# USB3_Replication.net
KiCad netlist of a schematic drawn in Altium Designer
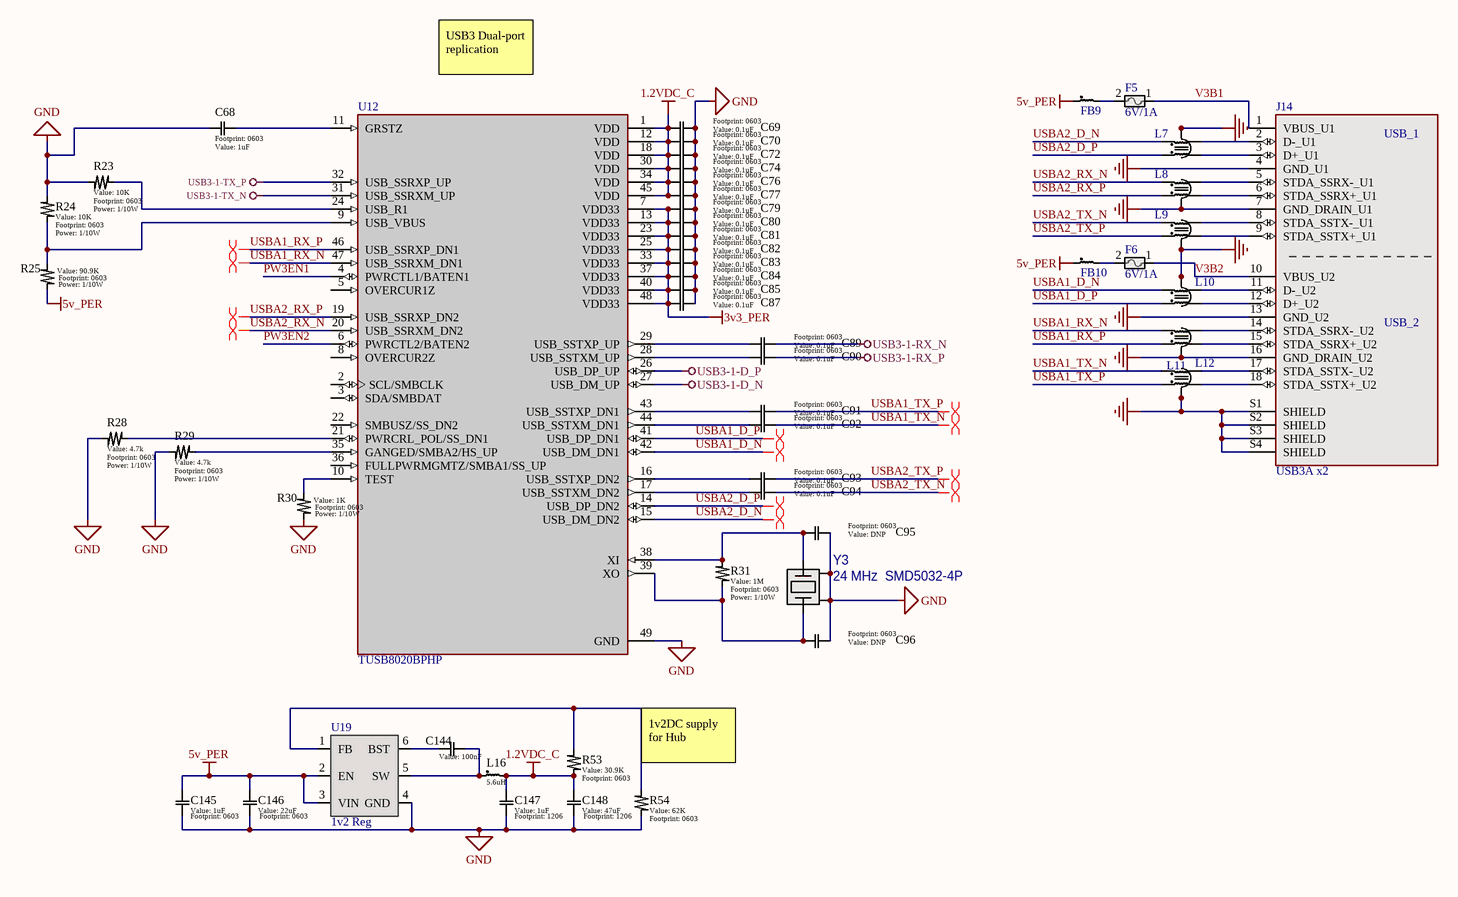
[diagram p0: USB3_Replication.SchDoc]

(export (version "E")
  (design (tool "Eeschema 10.0.6"))
  (components
    (comp (ref "C68")
      (value "1uF")
      (footprint "0603")
      (fields
        (field (name "VOLTAGE") ">10V")
        (field (name "TOLERANCE") "10%")
        (field (name "Comment") "Generic Capacitor")
      )
      (libsource (lib "Capacitors") (part "Generic Capacitor"))
    )
    (comp (ref "C69")
      (value "0.1uF")
      (footprint "0603")
      (fields
        (field (name "VOLTAGE") "10V")
        (field (name "TOLERANCE") "10%")
        (field (name "Comment") "Generic Capacitor")
      )
      (libsource (lib "Capacitors") (part "Generic Capacitor"))
    )
    (comp (ref "C70")
      (value "0.1uF")
      (footprint "0603")
      (fields
        (field (name "VOLTAGE") "10V")
        (field (name "TOLERANCE") "10%")
        (field (name "Comment") "Generic Capacitor")
      )
      (libsource (lib "Capacitors") (part "Generic Capacitor"))
    )
    (comp (ref "C72")
      (value "0.1uF")
      (footprint "0603")
      (fields
        (field (name "VOLTAGE") "10V")
        (field (name "TOLERANCE") "10%")
        (field (name "Comment") "Generic Capacitor")
      )
      (libsource (lib "Capacitors") (part "Generic Capacitor"))
    )
    (comp (ref "C74")
      (value "0.1uF")
      (footprint "0603")
      (fields
        (field (name "VOLTAGE") "10V")
        (field (name "TOLERANCE") "10%")
        (field (name "Comment") "Generic Capacitor")
      )
      (libsource (lib "Capacitors") (part "Generic Capacitor"))
    )
    (comp (ref "C76")
      (value "0.1uF")
      (footprint "0603")
      (fields
        (field (name "VOLTAGE") "10V")
        (field (name "TOLERANCE") "10%")
        (field (name "Comment") "Generic Capacitor")
      )
      (libsource (lib "Capacitors") (part "Generic Capacitor"))
    )
    (comp (ref "C77")
      (value "0.1uF")
      (footprint "0603")
      (fields
        (field (name "VOLTAGE") "10V")
        (field (name "TOLERANCE") "10%")
        (field (name "Comment") "Generic Capacitor")
      )
      (libsource (lib "Capacitors") (part "Generic Capacitor"))
    )
    (comp (ref "C79")
      (value "0.1uF")
      (footprint "0603")
      (fields
        (field (name "VOLTAGE") "10V")
        (field (name "TOLERANCE") "10%")
        (field (name "Comment") "Generic Capacitor")
      )
      (libsource (lib "Capacitors") (part "Generic Capacitor"))
    )
    (comp (ref "C80")
      (value "0.1uF")
      (footprint "0603")
      (fields
        (field (name "VOLTAGE") "10V")
        (field (name "TOLERANCE") "10%")
        (field (name "Comment") "Generic Capacitor")
      )
      (libsource (lib "Capacitors") (part "Generic Capacitor"))
    )
    (comp (ref "C81")
      (value "0.1uF")
      (footprint "0603")
      (fields
        (field (name "VOLTAGE") "10V")
        (field (name "TOLERANCE") "10%")
        (field (name "Comment") "Generic Capacitor")
      )
      (libsource (lib "Capacitors") (part "Generic Capacitor"))
    )
    (comp (ref "C82")
      (value "0.1uF")
      (footprint "0603")
      (fields
        (field (name "VOLTAGE") "10V")
        (field (name "TOLERANCE") "10%")
        (field (name "Comment") "Generic Capacitor")
      )
      (libsource (lib "Capacitors") (part "Generic Capacitor"))
    )
    (comp (ref "C83")
      (value "0.1uF")
      (footprint "0603")
      (fields
        (field (name "VOLTAGE") "10V")
        (field (name "TOLERANCE") "10%")
        (field (name "Comment") "Generic Capacitor")
      )
      (libsource (lib "Capacitors") (part "Generic Capacitor"))
    )
    (comp (ref "C84")
      (value "0.1uF")
      (footprint "0603")
      (fields
        (field (name "VOLTAGE") "10V")
        (field (name "TOLERANCE") "10%")
        (field (name "Comment") "Generic Capacitor")
      )
      (libsource (lib "Capacitors") (part "Generic Capacitor"))
    )
    (comp (ref "C85")
      (value "0.1uF")
      (footprint "0603")
      (fields
        (field (name "VOLTAGE") "10V")
        (field (name "TOLERANCE") "10%")
        (field (name "Comment") "Generic Capacitor")
      )
      (libsource (lib "Capacitors") (part "Generic Capacitor"))
    )
    (comp (ref "C87")
      (value "0.1uF")
      (footprint "0603")
      (fields
        (field (name "VOLTAGE") "10V")
        (field (name "TOLERANCE") "10%")
        (field (name "Comment") "Generic Capacitor")
      )
      (libsource (lib "Capacitors") (part "Generic Capacitor"))
    )
    (comp (ref "C89")
      (value "0.1uF")
      (footprint "0603")
      (fields
        (field (name "VOLTAGE") "10V")
        (field (name "TOLERANCE") "10%")
        (field (name "Comment") "Generic Capacitor")
      )
      (libsource (lib "Capacitors") (part "Generic Capacitor"))
    )
    (comp (ref "C90")
      (value "0.1uF")
      (footprint "0603")
      (fields
        (field (name "VOLTAGE") "10V")
        (field (name "TOLERANCE") "10%")
        (field (name "Comment") "Generic Capacitor")
      )
      (libsource (lib "Capacitors") (part "Generic Capacitor"))
    )
    (comp (ref "C91")
      (value "0.1uF")
      (footprint "0603")
      (fields
        (field (name "VOLTAGE") "10V")
        (field (name "TOLERANCE") "10%")
        (field (name "Comment") "Generic Capacitor")
      )
      (libsource (lib "Capacitors") (part "Generic Capacitor"))
    )
    (comp (ref "C92")
      (value "0.1uF")
      (footprint "0603")
      (fields
        (field (name "VOLTAGE") "10V")
        (field (name "TOLERANCE") "10%")
        (field (name "Comment") "Generic Capacitor")
      )
      (libsource (lib "Capacitors") (part "Generic Capacitor"))
    )
    (comp (ref "C93")
      (value "0.1uF")
      (footprint "0603")
      (fields
        (field (name "VOLTAGE") "10V")
        (field (name "TOLERANCE") "10%")
        (field (name "Comment") "Generic Capacitor")
      )
      (libsource (lib "Capacitors") (part "Generic Capacitor"))
    )
    (comp (ref "C94")
      (value "0.1uF")
      (footprint "0603")
      (fields
        (field (name "VOLTAGE") "10V")
        (field (name "TOLERANCE") "10%")
        (field (name "Comment") "Generic Capacitor")
      )
      (libsource (lib "Capacitors") (part "Generic Capacitor"))
    )
    (comp (ref "C95")
      (value "DNP")
      (footprint "0603")
      (fields
        (field (name "VOLTAGE") ">10V")
        (field (name "TOLERANCE") "10%")
        (field (name "Comment") "Generic Capacitor")
      )
      (libsource (lib "Capacitors") (part "Generic Capacitor"))
    )
    (comp (ref "C96")
      (value "DNP")
      (footprint "0603")
      (fields
        (field (name "VOLTAGE") ">10V")
        (field (name "TOLERANCE") "10%")
        (field (name "Comment") "Generic Capacitor")
      )
      (libsource (lib "Capacitors") (part "Generic Capacitor"))
    )
    (comp (ref "C144")
      (value "100nF")
      (footprint "0603")
      (fields
        (field (name "VOLTAGE") ">10V")
        (field (name "TOLERANCE") "10%")
        (field (name "Comment") "Generic Capacitor")
      )
      (libsource (lib "Capacitors") (part "Generic Capacitor"))
    )
    (comp (ref "C145")
      (value "1uF")
      (footprint "0603")
      (fields
        (field (name "VOLTAGE") ">10V")
        (field (name "TOLERANCE") "10%")
        (field (name "Comment") "Generic Capacitor")
      )
      (libsource (lib "Capacitors") (part "Generic Capacitor"))
    )
    (comp (ref "C146")
      (value "22uF")
      (footprint "0603")
      (fields
        (field (name "VOLTAGE") ">10V")
        (field (name "TOLERANCE") "10%")
        (field (name "Comment") "Generic Capacitor")
      )
      (libsource (lib "Capacitors") (part "Generic Capacitor"))
    )
    (comp (ref "C147")
      (value "1uF")
      (footprint "1206")
      (fields
        (field (name "VOLTAGE") ">10V")
        (field (name "TOLERANCE") "10%")
        (field (name "Comment") "Generic Capacitor")
      )
      (libsource (lib "Capacitors") (part "Generic Capacitor"))
    )
    (comp (ref "C148")
      (value "47uF")
      (footprint "1206")
      (fields
        (field (name "VOLTAGE") ">10V")
        (field (name "TOLERANCE") "10%")
        (field (name "Comment") "Generic Capacitor")
      )
      (libsource (lib "Capacitors") (part "Generic Capacitor"))
    )
    (comp (ref "F5")
      (value "6V/1A")
      (footprint "0805")
      (description "Polymeric PTC Resettable Fuse 6V 1 A Ih Surface Mount 0805 (2012 Metric), Concave")
      (fields (field (name "MANUFACTURER") "Bel") (field (name "MANUFACTURER PART NUMBER") "0ZCK0100FF2E"))
      (libsource (lib "Regulators") (part "0ZCK0100FF2E"))
    )
    (comp (ref "F6")
      (value "6V/1A")
      (footprint "0805")
      (description "Polymeric PTC Resettable Fuse 6V 1 A Ih Surface Mount 0805 (2012 Metric), Concave")
      (fields (field (name "MANUFACTURER") "Bel") (field (name "MANUFACTURER PART NUMBER") "0ZCK0100FF2E"))
      (libsource (lib "Regulators") (part "0ZCK0100FF2E"))
    )
    (comp (ref "FB9")
      (value "0603 Ferrite")
      (footprint "0603")
      (description "120 Ohms @ 100 MHz 1 Signal Line Ferrite Bead 0603 (1608 Metric) 500mA 180mOhm")
      (fields
        (field (name "MANUFACTURER") "Pulse")
        (field (name "MANUFACTURER PART NUMBER") "PE-0603FB121ST")
      )
      (libsource (lib "Inductors") (part "PE-0603FB121ST"))
    )
    (comp (ref "FB10")
      (value "0603 Ferrite")
      (footprint "0603")
      (description "120 Ohms @ 100 MHz 1 Signal Line Ferrite Bead 0603 (1608 Metric) 500mA 180mOhm")
      (fields
        (field (name "MANUFACTURER") "Pulse")
        (field (name "MANUFACTURER PART NUMBER") "PE-0603FB121ST")
      )
      (libsource (lib "Inductors") (part "PE-0603FB121ST"))
    )
    (comp (ref "J14")
      (value "USB3A x2")
      (footprint "0484060003")
      (fields (field (name "MP") "0484060003") (field (name "MF") "Molex"))
      (libsource (lib "Connectors") (part "0484060003"))
    )
    (comp (ref "L7")
      (value "2CH CMC")
      (footprint "SMD-6-2CH")
      (description "35Ω@100MHz -40℃~+85℃ 4Ω 5V 2 100mA SMD Common Mode Filters ROHS")
      (libsource (lib "Inductors") (part "ICMEF112P350MFR"))
    )
    (comp (ref "L8")
      (value "2CH CMC")
      (footprint "SMD-6-2CH")
      (description "35Ω@100MHz -40℃~+85℃ 4Ω 5V 2 100mA SMD Common Mode Filters ROHS")
      (libsource (lib "") (part "ICMEF112P350MFR_1"))
    )
    (comp (ref "L9")
      (value "2CH CMC")
      (footprint "SMD-6-2CH")
      (description "35Ω@100MHz -40℃~+85℃ 4Ω 5V 2 100mA SMD Common Mode Filters ROHS")
      (libsource (lib "") (part "ICMEF112P350MFR_1"))
    )
    (comp (ref "L10")
      (value "2CH CMC")
      (footprint "SMD-6-2CH")
      (description "35Ω@100MHz -40℃~+85℃ 4Ω 5V 2 100mA SMD Common Mode Filters ROHS")
      (libsource (lib "Inductors") (part "ICMEF112P350MFR"))
    )
    (comp (ref "L11")
      (value "2CH CMC")
      (footprint "SMD-6-2CH")
      (description "35Ω@100MHz -40℃~+85℃ 4Ω 5V 2 100mA SMD Common Mode Filters ROHS")
      (libsource (lib "") (part "ICMEF112P350MFR_1"))
    )
    (comp (ref "L12")
      (value "2CH CMC")
      (footprint "SMD-6-2CH")
      (description "35Ω@100MHz -40℃~+85℃ 4Ω 5V 2 100mA SMD Common Mode Filters ROHS")
      (libsource (lib "") (part "ICMEF112P350MFR_1"))
    )
    (comp (ref "L16")
      (value "5.6uH")
      (footprint "TMPC0402HP")
      (description "2A 5.6uH ±20% SMD Power Inductor")
      (libsource (lib "Inductors") (part "TMPC0402HP-5R6MG-Z02"))
    )
    (comp (ref "R23")
      (value "10K")
      (footprint "0603")
      (fields
        (field (name "TOLERANCE") "1%")
        (field (name "POWER") "1/10W")
        (field (name "Comment") "Generic Resistor")
      )
      (libsource (lib "Resistors") (part "Generic Resistor"))
    )
    (comp (ref "R24")
      (value "10K")
      (footprint "0603")
      (fields
        (field (name "TOLERANCE") "1%")
        (field (name "POWER") "1/10W")
        (field (name "Comment") "Generic Resistor")
      )
      (libsource (lib "Resistors") (part "Generic Resistor"))
    )
    (comp (ref "R25")
      (value "90.9K")
      (footprint "0603")
      (fields
        (field (name "TOLERANCE") "1%")
        (field (name "POWER") "1/10W")
        (field (name "Comment") "Generic Resistor")
      )
      (libsource (lib "Resistors") (part "Generic Resistor"))
    )
    (comp (ref "R28")
      (value "4.7k")
      (footprint "0603")
      (fields
        (field (name "TOLERANCE") "1%")
        (field (name "POWER") "1/10W")
        (field (name "Comment") "Generic Resistor")
      )
      (libsource (lib "Resistors") (part "Generic Resistor"))
    )
    (comp (ref "R29")
      (value "4.7k")
      (footprint "0603")
      (fields
        (field (name "TOLERANCE") "1%")
        (field (name "POWER") "1/10W")
        (field (name "Comment") "Generic Resistor")
      )
      (libsource (lib "Resistors") (part "Generic Resistor"))
    )
    (comp (ref "R30")
      (value "1K")
      (footprint "0603")
      (fields
        (field (name "TOLERANCE") "1%")
        (field (name "POWER") "1/10W")
        (field (name "Comment") "Generic Resistor")
      )
      (libsource (lib "Resistors") (part "Generic Resistor"))
    )
    (comp (ref "R31")
      (value "1M")
      (footprint "0603")
      (fields
        (field (name "TOLERANCE") "1%")
        (field (name "POWER") "1/10W")
        (field (name "Comment") "Generic Resistor")
      )
      (libsource (lib "Resistors") (part "Generic Resistor"))
    )
    (comp (ref "R53")
      (value "30.9K")
      (footprint "0603")
      (fields
        (field (name "TOLERANCE") "1%")
        (field (name "POWER") "1/10W")
        (field (name "Comment") "Generic Resistor")
      )
      (libsource (lib "Resistors") (part "Generic Resistor"))
    )
    (comp (ref "R54")
      (value "62K")
      (footprint "0603")
      (fields
        (field (name "TOLERANCE") "1%")
        (field (name "POWER") "1/10W")
        (field (name "Comment") "Generic Resistor")
      )
      (libsource (lib "Resistors") (part "Generic Resistor"))
    )
    (comp (ref "U12")
      (value "TUSB8020BPHP")
      (footprint "HTQFP-48(7x7)")
      (description "USB Hub Controller USB 3.0")
      (libsource (lib "Misc ICs") (part "TUSB8020BPHP"))
    )
    (comp (ref "U19")
      (value "1v2 Reg")
      (footprint "TSOT-23-6")
      (description "Step-down type Adjustable 2A 1.2V~12V 3.8V~32V TSOT-23-6 DC-DC Converter")
      (libsource (lib "Regulators") (part "AP63201WU-7"))
    )
    (comp (ref "Y3")
      (value "24 MHz  SMD5032-4P")
      (footprint "ECS-240-18-30BQ-DS")
      (description "24 MHz ±30ppm Crystal 18pF 30 Ohms 4-SMD, No Lead")
      (libsource (lib "Gamber - Johnson LLC") (part "ECS-240-18-30BQ-DS"))
    )
  )
  (nets
    (net (code "1") (name "/PW3EN1") (class "Default")
      (node (ref "U12") (pin "4") (pinfunction "PWRCTL1/BATEN1_4") (pintype "bidirectional"))
    )
    (net (code "2") (name "/PW3EN2") (class "Default")
      (node (ref "U12") (pin "6") (pinfunction "PWRCTL2/BATEN2_6") (pintype "bidirectional"))
    )
    (net (code "3") (name "/USBA1_D_N") (class "Default")
      (node (ref "L10") (pin "2") (pinfunction "2_2") (pintype "passive"))
      (node (ref "U12") (pin "42") (pinfunction "USB_DM_DN1_42") (pintype "bidirectional"))
    )
    (net (code "4") (name "/USBA1_D_P") (class "Default")
      (node (ref "L10") (pin "1") (pinfunction "1_1") (pintype "passive"))
      (node (ref "U12") (pin "41") (pinfunction "USB_DP_DN1_41") (pintype "bidirectional"))
    )
    (net (code "5") (name "/USBA1_RX_N") (class "Default")
      (node (ref "L11") (pin "1") (pinfunction "1_1") (pintype "passive"))
      (node (ref "U12") (pin "47") (pinfunction "USB_SSRXM_DN1_47") (pintype "input"))
    )
    (net (code "6") (name "/USBA1_RX_P") (class "Default")
      (node (ref "L11") (pin "2") (pinfunction "2_2") (pintype "passive"))
      (node (ref "U12") (pin "46") (pinfunction "USB_SSRXP_DN1_46") (pintype "input"))
    )
    (net (code "7") (name "/USBA1_TX_N") (class "Default")
      (node (ref "C92") (pin "1") (pinfunction "1_1") (pintype "passive"))
      (node (ref "L12") (pin "1") (pinfunction "1_1") (pintype "passive"))
    )
    (net (code "8") (name "/USBA1_TX_P") (class "Default")
      (node (ref "C91") (pin "1") (pinfunction "1_1") (pintype "passive"))
      (node (ref "L12") (pin "2") (pinfunction "2_2") (pintype "passive"))
    )
    (net (code "9") (name "/USBA2_D_N") (class "Default")
      (node (ref "L7") (pin "2") (pinfunction "2_2") (pintype "passive"))
      (node (ref "U12") (pin "15") (pinfunction "USB_DM_DN2_15") (pintype "bidirectional"))
    )
    (net (code "10") (name "/USBA2_D_P") (class "Default")
      (node (ref "L7") (pin "1") (pinfunction "1_1") (pintype "passive"))
      (node (ref "U12") (pin "14") (pinfunction "USB_DP_DN2_14") (pintype "bidirectional"))
    )
    (net (code "11") (name "/USBA2_RX_N") (class "Default")
      (node (ref "L8") (pin "1") (pinfunction "1_1") (pintype "passive"))
      (node (ref "U12") (pin "20") (pinfunction "USB_SSRXM_DN2_20") (pintype "input"))
    )
    (net (code "12") (name "/USBA2_RX_P") (class "Default")
      (node (ref "L8") (pin "2") (pinfunction "2_2") (pintype "passive"))
      (node (ref "U12") (pin "19") (pinfunction "USB_SSRXP_DN2_19") (pintype "input"))
    )
    (net (code "13") (name "/USBA2_TX_N") (class "Default")
      (node (ref "C94") (pin "1") (pinfunction "1_1") (pintype "passive"))
      (node (ref "L9") (pin "1") (pinfunction "1_1") (pintype "passive"))
    )
    (net (code "14") (name "/USBA2_TX_P") (class "Default")
      (node (ref "C93") (pin "1") (pinfunction "1_1") (pintype "passive"))
      (node (ref "L9") (pin "2") (pinfunction "2_2") (pintype "passive"))
    )
    (net (code "15") (name "/V3B1") (class "Default")
      (node (ref "F5") (pin "1") (pinfunction "1_1") (pintype "passive"))
      (node (ref "J14") (pin "1") (pinfunction "VBUS_U1_1") (pintype "power_in"))
    )
    (net (code "16") (name "/V3B2") (class "Default")
      (node (ref "F6") (pin "1") (pinfunction "1_1") (pintype "passive"))
      (node (ref "J14") (pin "10") (pinfunction "VBUS_U2_10") (pintype "power_in"))
    )
    (net (code "17") (name "1.2VDC_C") (class "Default")
      (node (ref "C147") (pin "1") (pinfunction "1_1") (pintype "passive"))
      (node (ref "C148") (pin "1") (pinfunction "1_1") (pintype "passive"))
      (node (ref "C69") (pin "2") (pinfunction "2_2") (pintype "passive"))
      (node (ref "C70") (pin "2") (pinfunction "2_2") (pintype "passive"))
      (node (ref "C72") (pin "2") (pinfunction "2_2") (pintype "passive"))
      (node (ref "C74") (pin "2") (pinfunction "2_2") (pintype "passive"))
      (node (ref "C76") (pin "2") (pinfunction "2_2") (pintype "passive"))
      (node (ref "C77") (pin "2") (pinfunction "2_2") (pintype "passive"))
      (node (ref "L16") (pin "2") (pinfunction "2_2") (pintype "passive"))
      (node (ref "R53") (pin "1") (pinfunction "1_1") (pintype "passive"))
      (node (ref "U12") (pin "1") (pinfunction "VDD_1") (pintype "power_in"))
      (node (ref "U12") (pin "12") (pinfunction "VDD_12") (pintype "power_in"))
      (node (ref "U12") (pin "18") (pinfunction "VDD_18") (pintype "power_in"))
      (node (ref "U12") (pin "30") (pinfunction "VDD_30") (pintype "power_in"))
      (node (ref "U12") (pin "34") (pinfunction "VDD_34") (pintype "power_in"))
      (node (ref "U12") (pin "45") (pinfunction "VDD_45") (pintype "power_in"))
    )
    (net (code "18") (name "3v3_PER") (class "Default")
      (node (ref "C79") (pin "2") (pinfunction "2_2") (pintype "passive"))
      (node (ref "C80") (pin "2") (pinfunction "2_2") (pintype "passive"))
      (node (ref "C81") (pin "2") (pinfunction "2_2") (pintype "passive"))
      (node (ref "C82") (pin "2") (pinfunction "2_2") (pintype "passive"))
      (node (ref "C83") (pin "2") (pinfunction "2_2") (pintype "passive"))
      (node (ref "C84") (pin "2") (pinfunction "2_2") (pintype "passive"))
      (node (ref "C85") (pin "2") (pinfunction "2_2") (pintype "passive"))
      (node (ref "C87") (pin "2") (pinfunction "2_2") (pintype "passive"))
      (node (ref "U12") (pin "13") (pinfunction "VDD33_13") (pintype "power_in"))
      (node (ref "U12") (pin "23") (pinfunction "VDD33_23") (pintype "power_in"))
      (node (ref "U12") (pin "25") (pinfunction "VDD33_25") (pintype "power_in"))
      (node (ref "U12") (pin "33") (pinfunction "VDD33_33") (pintype "power_in"))
      (node (ref "U12") (pin "37") (pinfunction "VDD33_37") (pintype "power_in"))
      (node (ref "U12") (pin "40") (pinfunction "VDD33_40") (pintype "power_in"))
      (node (ref "U12") (pin "48") (pinfunction "VDD33_48") (pintype "power_in"))
      (node (ref "U12") (pin "7") (pinfunction "VDD33_7") (pintype "power_in"))
    )
    (net (code "19") (name "5v_PER") (class "Default")
      (node (ref "C145") (pin "1") (pinfunction "1_1") (pintype "passive"))
      (node (ref "C146") (pin "1") (pinfunction "1_1") (pintype "passive"))
      (node (ref "FB10") (pin "1") (pinfunction "1_1") (pintype "passive"))
      (node (ref "FB9") (pin "1") (pinfunction "1_1") (pintype "passive"))
      (node (ref "R25") (pin "1") (pinfunction "1_1") (pintype "passive"))
      (node (ref "U19") (pin "2") (pinfunction "EN_2") (pintype "passive"))
      (node (ref "U19") (pin "3") (pinfunction "VIN_3") (pintype "passive"))
    )
    (net (code "20") (name "GND") (class "Default")
      (node (ref "C145") (pin "2") (pinfunction "2_2") (pintype "passive"))
      (node (ref "C146") (pin "2") (pinfunction "2_2") (pintype "passive"))
      (node (ref "C147") (pin "2") (pinfunction "2_2") (pintype "passive"))
      (node (ref "C148") (pin "2") (pinfunction "2_2") (pintype "passive"))
      (node (ref "C68") (pin "1") (pinfunction "1_1") (pintype "passive"))
      (node (ref "C69") (pin "1") (pinfunction "1_1") (pintype "passive"))
      (node (ref "C70") (pin "1") (pinfunction "1_1") (pintype "passive"))
      (node (ref "C72") (pin "1") (pinfunction "1_1") (pintype "passive"))
      (node (ref "C74") (pin "1") (pinfunction "1_1") (pintype "passive"))
      (node (ref "C76") (pin "1") (pinfunction "1_1") (pintype "passive"))
      (node (ref "C77") (pin "1") (pinfunction "1_1") (pintype "passive"))
      (node (ref "C79") (pin "1") (pinfunction "1_1") (pintype "passive"))
      (node (ref "C80") (pin "1") (pinfunction "1_1") (pintype "passive"))
      (node (ref "C81") (pin "1") (pinfunction "1_1") (pintype "passive"))
      (node (ref "C82") (pin "1") (pinfunction "1_1") (pintype "passive"))
      (node (ref "C83") (pin "1") (pinfunction "1_1") (pintype "passive"))
      (node (ref "C84") (pin "1") (pinfunction "1_1") (pintype "passive"))
      (node (ref "C85") (pin "1") (pinfunction "1_1") (pintype "passive"))
      (node (ref "C87") (pin "1") (pinfunction "1_1") (pintype "passive"))
      (node (ref "C95") (pin "1") (pinfunction "1_1") (pintype "passive"))
      (node (ref "C96") (pin "1") (pinfunction "1_1") (pintype "passive"))
      (node (ref "J14") (pin "13") (pinfunction "GND_U2_13") (pintype "power_in"))
      (node (ref "J14") (pin "16") (pinfunction "GND_DRAIN_U2_16") (pintype "power_in"))
      (node (ref "J14") (pin "4") (pinfunction "GND_U1_4") (pintype "power_in"))
      (node (ref "J14") (pin "7") (pinfunction "GND_DRAIN_U1_7") (pintype "power_in"))
      (node (ref "J14") (pin "S1") (pinfunction "SHIELD_S1") (pintype "passive"))
      (node (ref "J14") (pin "S2") (pinfunction "SHIELD_S2") (pintype "passive"))
      (node (ref "J14") (pin "S3") (pinfunction "SHIELD_S3") (pintype "passive"))
      (node (ref "J14") (pin "S4") (pinfunction "SHIELD_S4") (pintype "passive"))
      (node (ref "L10") (pin "5") (pinfunction "5_5") (pintype "passive"))
      (node (ref "L10") (pin "6") (pinfunction "6_6") (pintype "passive"))
      (node (ref "L11") (pin "5") (pinfunction "5_5") (pintype "passive"))
      (node (ref "L11") (pin "6") (pinfunction "6_6") (pintype "passive"))
      (node (ref "L12") (pin "5") (pinfunction "5_5") (pintype "passive"))
      (node (ref "L12") (pin "6") (pinfunction "6_6") (pintype "passive"))
      (node (ref "L7") (pin "5") (pinfunction "5_5") (pintype "passive"))
      (node (ref "L7") (pin "6") (pinfunction "6_6") (pintype "passive"))
      (node (ref "L8") (pin "5") (pinfunction "5_5") (pintype "passive"))
      (node (ref "L8") (pin "6") (pinfunction "6_6") (pintype "passive"))
      (node (ref "L9") (pin "5") (pinfunction "5_5") (pintype "passive"))
      (node (ref "L9") (pin "6") (pinfunction "6_6") (pintype "passive"))
      (node (ref "R23") (pin "1") (pinfunction "1_1") (pintype "passive"))
      (node (ref "R24") (pin "1") (pinfunction "1_1") (pintype "passive"))
      (node (ref "R28") (pin "1") (pinfunction "1_1") (pintype "passive"))
      (node (ref "R29") (pin "1") (pinfunction "1_1") (pintype "passive"))
      (node (ref "R30") (pin "1") (pinfunction "1_1") (pintype "passive"))
      (node (ref "R54") (pin "1") (pinfunction "1_1") (pintype "passive"))
      (node (ref "U12") (pin "49") (pinfunction "GND_49") (pintype "power_in"))
      (node (ref "U19") (pin "4") (pinfunction "GND_4") (pintype "power_in"))
      (node (ref "Y3") (pin "2") (pinfunction "GND_2") (pintype "power_in"))
      (node (ref "Y3") (pin "4") (pinfunction "GND_4") (pintype "power_in"))
    )
    (net (code "21") (name "Net-(F5-Pad2)") (class "Default")
      (node (ref "F5") (pin "2") (pinfunction "2_2") (pintype "passive"))
      (node (ref "FB9") (pin "2") (pinfunction "2_2") (pintype "passive"))
    )
    (net (code "22") (name "Net-(F6-Pad2)") (class "Default")
      (node (ref "F6") (pin "2") (pinfunction "2_2") (pintype "passive"))
      (node (ref "FB10") (pin "2") (pinfunction "2_2") (pintype "passive"))
    )
    (net (code "23") (name "Net-(J14-D+_U1)") (class "Default")
      (node (ref "J14") (pin "3") (pinfunction "D+_U1_3") (pintype "bidirectional"))
      (node (ref "L7") (pin "4") (pinfunction "4_4") (pintype "passive"))
    )
    (net (code "24") (name "Net-(J14-D+_U2)") (class "Default")
      (node (ref "J14") (pin "12") (pinfunction "D+_U2_12") (pintype "bidirectional"))
      (node (ref "L10") (pin "4") (pinfunction "4_4") (pintype "passive"))
    )
    (net (code "25") (name "Net-(J14-D-_U1)") (class "Default")
      (node (ref "J14") (pin "2") (pinfunction "D-_U1_2") (pintype "bidirectional"))
      (node (ref "L7") (pin "3") (pinfunction "3_3") (pintype "passive"))
    )
    (net (code "26") (name "Net-(J14-D-_U2)") (class "Default")
      (node (ref "J14") (pin "11") (pinfunction "D-_U2_11") (pintype "bidirectional"))
      (node (ref "L10") (pin "3") (pinfunction "3_3") (pintype "passive"))
    )
    (net (code "27") (name "Net-(J14-STDA_SSRX+_U1)") (class "Default")
      (node (ref "J14") (pin "6") (pinfunction "STDA_SSRX+_U1_6") (pintype "bidirectional"))
      (node (ref "L8") (pin "3") (pinfunction "3_3") (pintype "passive"))
    )
    (net (code "28") (name "Net-(J14-STDA_SSRX+_U2)") (class "Default")
      (node (ref "J14") (pin "15") (pinfunction "STDA_SSRX+_U2_15") (pintype "bidirectional"))
      (node (ref "L11") (pin "3") (pinfunction "3_3") (pintype "passive"))
    )
    (net (code "29") (name "Net-(J14-STDA_SSRX-_U1)") (class "Default")
      (node (ref "J14") (pin "5") (pinfunction "STDA_SSRX-_U1_5") (pintype "bidirectional"))
      (node (ref "L8") (pin "4") (pinfunction "4_4") (pintype "passive"))
    )
    (net (code "30") (name "Net-(J14-STDA_SSRX-_U2)") (class "Default")
      (node (ref "J14") (pin "14") (pinfunction "STDA_SSRX-_U2_14") (pintype "bidirectional"))
      (node (ref "L11") (pin "4") (pinfunction "4_4") (pintype "passive"))
    )
    (net (code "31") (name "Net-(J14-STDA_SSTX+_U1)") (class "Default")
      (node (ref "J14") (pin "9") (pinfunction "STDA_SSTX+_U1_9") (pintype "bidirectional"))
      (node (ref "L9") (pin "3") (pinfunction "3_3") (pintype "passive"))
    )
    (net (code "32") (name "Net-(J14-STDA_SSTX+_U2)") (class "Default")
      (node (ref "J14") (pin "18") (pinfunction "STDA_SSTX+_U2_18") (pintype "bidirectional"))
      (node (ref "L12") (pin "3") (pinfunction "3_3") (pintype "passive"))
    )
    (net (code "33") (name "Net-(J14-STDA_SSTX-_U1)") (class "Default")
      (node (ref "J14") (pin "8") (pinfunction "STDA_SSTX-_U1_8") (pintype "bidirectional"))
      (node (ref "L9") (pin "4") (pinfunction "4_4") (pintype "passive"))
    )
    (net (code "34") (name "Net-(J14-STDA_SSTX-_U2)") (class "Default")
      (node (ref "J14") (pin "17") (pinfunction "STDA_SSTX-_U2_17") (pintype "bidirectional"))
      (node (ref "L12") (pin "4") (pinfunction "4_4") (pintype "passive"))
    )
    (net (code "35") (name "Net-(U12-GANGED{slash}SMBA2{slash}HS_UP)") (class "Default")
      (node (ref "R29") (pin "2") (pinfunction "2_2") (pintype "passive"))
      (node (ref "U12") (pin "35") (pinfunction "GANGED/SMBA2/HS_UP_35") (pintype "input"))
    )
    (net (code "36") (name "Net-(U12-GRSTZ)") (class "Default")
      (node (ref "C68") (pin "2") (pinfunction "2_2") (pintype "passive"))
      (node (ref "U12") (pin "11") (pinfunction "GRSTZ_11") (pintype "input"))
    )
    (net (code "37") (name "Net-(U12-PWRCRL_POL{slash}SS_DN1)") (class "Default")
      (node (ref "R28") (pin "2") (pinfunction "2_2") (pintype "passive"))
      (node (ref "U12") (pin "21") (pinfunction "PWRCRL_POL/SS_DN1_21") (pintype "bidirectional"))
    )
    (net (code "38") (name "Net-(U12-TEST)") (class "Default")
      (node (ref "R30") (pin "2") (pinfunction "2_2") (pintype "passive"))
      (node (ref "U12") (pin "10") (pinfunction "TEST_10") (pintype "input"))
    )
    (net (code "39") (name "Net-(U12-USB_R1)") (class "Default")
      (node (ref "R23") (pin "2") (pinfunction "2_2") (pintype "passive"))
      (node (ref "U12") (pin "24") (pinfunction "USB_R1_24") (pintype "input"))
    )
    (net (code "40") (name "Net-(U12-USB_SSTXM_DN1)") (class "Default")
      (node (ref "C92") (pin "2") (pinfunction "2_2") (pintype "passive"))
      (node (ref "U12") (pin "44") (pinfunction "USB_SSTXM_DN1_44") (pintype "output"))
    )
    (net (code "41") (name "Net-(U12-USB_SSTXM_DN2)") (class "Default")
      (node (ref "C94") (pin "2") (pinfunction "2_2") (pintype "passive"))
      (node (ref "U12") (pin "17") (pinfunction "USB_SSTXM_DN2_17") (pintype "output"))
    )
    (net (code "42") (name "Net-(U12-USB_SSTXM_UP)") (class "Default")
      (node (ref "C90") (pin "2") (pinfunction "2_2") (pintype "passive"))
      (node (ref "U12") (pin "28") (pinfunction "USB_SSTXM_UP_28") (pintype "output"))
    )
    (net (code "43") (name "Net-(U12-USB_SSTXP_DN1)") (class "Default")
      (node (ref "C91") (pin "2") (pinfunction "2_2") (pintype "passive"))
      (node (ref "U12") (pin "43") (pinfunction "USB_SSTXP_DN1_43") (pintype "output"))
    )
    (net (code "44") (name "Net-(U12-USB_SSTXP_DN2)") (class "Default")
      (node (ref "C93") (pin "2") (pinfunction "2_2") (pintype "passive"))
      (node (ref "U12") (pin "16") (pinfunction "USB_SSTXP_DN2_16") (pintype "output"))
    )
    (net (code "45") (name "Net-(U12-USB_SSTXP_UP)") (class "Default")
      (node (ref "C89") (pin "2") (pinfunction "2_2") (pintype "passive"))
      (node (ref "U12") (pin "29") (pinfunction "USB_SSTXP_UP_29") (pintype "output"))
    )
    (net (code "46") (name "Net-(U12-USB_VBUS)") (class "Default")
      (node (ref "R24") (pin "2") (pinfunction "2_2") (pintype "passive"))
      (node (ref "R25") (pin "2") (pinfunction "2_2") (pintype "passive"))
      (node (ref "U12") (pin "9") (pinfunction "USB_VBUS_9") (pintype "input"))
    )
    (net (code "47") (name "Net-(U12-XI)") (class "Default")
      (node (ref "C95") (pin "2") (pinfunction "2_2") (pintype "passive"))
      (node (ref "R31") (pin "1") (pinfunction "1_1") (pintype "passive"))
      (node (ref "U12") (pin "38") (pinfunction "XI_38") (pintype "input"))
      (node (ref "Y3") (pin "3") (pintype "passive"))
    )
    (net (code "48") (name "Net-(U12-XO)") (class "Default")
      (node (ref "C96") (pin "2") (pinfunction "2_2") (pintype "passive"))
      (node (ref "R31") (pin "2") (pinfunction "2_2") (pintype "passive"))
      (node (ref "U12") (pin "39") (pinfunction "XO_39") (pintype "output"))
      (node (ref "Y3") (pin "1") (pintype "passive"))
    )
    (net (code "49") (name "Net-(U19-BST)") (class "Default")
      (node (ref "C144") (pin "1") (pinfunction "1_1") (pintype "passive"))
      (node (ref "U19") (pin "6") (pinfunction "BST_6") (pintype "passive"))
    )
    (net (code "50") (name "Net-(U19-FB)") (class "Default")
      (node (ref "R53") (pin "2") (pinfunction "2_2") (pintype "passive"))
      (node (ref "R54") (pin "2") (pinfunction "2_2") (pintype "passive"))
      (node (ref "U19") (pin "1") (pinfunction "FB_1") (pintype "passive"))
    )
    (net (code "51") (name "Net-(U19-SW)") (class "Default")
      (node (ref "C144") (pin "2") (pinfunction "2_2") (pintype "passive"))
      (node (ref "L16") (pin "1") (pinfunction "1_1") (pintype "passive"))
      (node (ref "U19") (pin "5") (pinfunction "SW_5") (pintype "passive"))
    )
    (net (code "52") (name "USB3-1-D_N") (class "Default")
      (node (ref "U12") (pin "27") (pinfunction "USB_DM_UP_27") (pintype "bidirectional"))
    )
    (net (code "53") (name "USB3-1-D_P") (class "Default")
      (node (ref "U12") (pin "26") (pinfunction "USB_DP_UP_26") (pintype "bidirectional"))
    )
    (net (code "54") (name "USB3-1-RX_N") (class "Default")
      (node (ref "C89") (pin "1") (pinfunction "1_1") (pintype "passive"))
    )
    (net (code "55") (name "USB3-1-RX_P") (class "Default")
      (node (ref "C90") (pin "1") (pinfunction "1_1") (pintype "passive"))
    )
    (net (code "56") (name "USB3-1-TX_N") (class "Default")
      (node (ref "U12") (pin "31") (pinfunction "USB_SSRXM_UP_31") (pintype "input"))
    )
    (net (code "57") (name "USB3-1-TX_P") (class "Default")
      (node (ref "U12") (pin "32") (pinfunction "USB_SSRXP_UP_32") (pintype "input"))
    )
    (net (code "58") (name "unconnected-(U12-FULLPWRMGMTZ{slash}SMBA1{slash}SS_UP-Pad36)") (class "Default")
      (node (ref "U12") (pin "36") (pinfunction "FULLPWRMGMTZ/SMBA1/SS_UP_36") (pintype "input"))
    )
    (net (code "59") (name "unconnected-(U12-OVERCUR1Z-Pad5)") (class "Default")
      (node (ref "U12") (pin "5") (pinfunction "OVERCUR1Z_5") (pintype "input"))
    )
    (net (code "60") (name "unconnected-(U12-OVERCUR2Z-Pad8)") (class "Default")
      (node (ref "U12") (pin "8") (pinfunction "OVERCUR2Z_8") (pintype "input"))
    )
    (net (code "61") (name "unconnected-(U12-SCL{slash}SMBCLK-Pad2)") (class "Default")
      (node (ref "U12") (pin "2") (pinfunction "SCL/SMBCLK_2") (pintype "bidirectional"))
    )
    (net (code "62") (name "unconnected-(U12-SDA{slash}SMBDAT-Pad3)") (class "Default")
      (node (ref "U12") (pin "3") (pinfunction "SDA/SMBDAT_3") (pintype "bidirectional"))
    )
    (net (code "63") (name "unconnected-(U12-SMBUSZ{slash}SS_DN2-Pad22)") (class "Default")
      (node (ref "U12") (pin "22") (pinfunction "SMBUSZ/SS_DN2_22") (pintype "input"))
    )
  )
)
